# power.net
KiCad netlist of a schematic drawn in Altium Designer
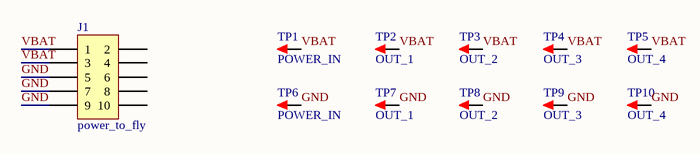
[diagram p0: power.SchDoc]

(export (version "E")
  (design (tool "Eeschema 10.0.6"))
  (components
    (comp (ref "J1")
      (value "power_to_fly")
      (footprint "HDR1.27 2x5-M-SMD")
      (description "2x5P-接插件")
      (fields (field (name "MANUFACTURER_PART_NUMBER") "826656-5"))
      (libsource (lib "mySchLib") (part "Header_2x5"))
    )
    (comp (ref "TP1")
      (value "POWER_IN")
      (footprint "test_2")
      (description "测试点")
      (fields (field (name "版权归属") "源创客"))
      (libsource (lib "Schlib") (part "TEST"))
    )
    (comp (ref "TP2")
      (value "OUT_1")
      (footprint "test_1")
      (description "测试点")
      (fields (field (name "版权归属") "源创客"))
      (libsource (lib "Schlib") (part "TEST"))
    )
    (comp (ref "TP3")
      (value "OUT_2")
      (footprint "test_1")
      (description "测试点")
      (fields (field (name "版权归属") "源创客"))
      (libsource (lib "Schlib") (part "TEST"))
    )
    (comp (ref "TP4")
      (value "OUT_3")
      (footprint "test_1")
      (description "测试点")
      (fields (field (name "版权归属") "源创客"))
      (libsource (lib "Schlib") (part "TEST"))
    )
    (comp (ref "TP5")
      (value "OUT_4")
      (footprint "test_1")
      (description "测试点")
      (fields (field (name "版权归属") "源创客"))
      (libsource (lib "Schlib") (part "TEST"))
    )
    (comp (ref "TP6")
      (value "POWER_IN")
      (footprint "test_2")
      (description "测试点")
      (fields (field (name "版权归属") "源创客"))
      (libsource (lib "Schlib") (part "TEST"))
    )
    (comp (ref "TP7")
      (value "OUT_1")
      (footprint "test_1")
      (description "测试点")
      (fields (field (name "版权归属") "源创客"))
      (libsource (lib "Schlib") (part "TEST"))
    )
    (comp (ref "TP8")
      (value "OUT_2")
      (footprint "test_1")
      (description "测试点")
      (fields (field (name "版权归属") "源创客"))
      (libsource (lib "Schlib") (part "TEST"))
    )
    (comp (ref "TP9")
      (value "OUT_3")
      (footprint "test_1")
      (description "测试点")
      (fields (field (name "版权归属") "源创客"))
      (libsource (lib "Schlib") (part "TEST"))
    )
    (comp (ref "TP10")
      (value "OUT_4")
      (footprint "test_1")
      (description "测试点")
      (fields (field (name "版权归属") "源创客"))
      (libsource (lib "Schlib") (part "TEST"))
    )
  )
  (nets
    (net (code "1") (name "/GND") (class "Default")
      (node (ref "J1") (pin "5") (pinfunction "5_5") (pintype "passive"))
      (node (ref "J1") (pin "7") (pinfunction "7_7") (pintype "passive"))
      (node (ref "J1") (pin "9") (pinfunction "9_9") (pintype "passive"))
      (node (ref "TP10") (pin "1") (pinfunction "1_1") (pintype "passive"))
      (node (ref "TP6") (pin "1") (pinfunction "1_1") (pintype "passive"))
      (node (ref "TP7") (pin "1") (pinfunction "1_1") (pintype "passive"))
      (node (ref "TP8") (pin "1") (pinfunction "1_1") (pintype "passive"))
      (node (ref "TP9") (pin "1") (pinfunction "1_1") (pintype "passive"))
    )
    (net (code "2") (name "/VBAT") (class "Default")
      (node (ref "J1") (pin "1") (pinfunction "1_1") (pintype "passive"))
      (node (ref "J1") (pin "3") (pinfunction "3_3") (pintype "passive"))
      (node (ref "TP1") (pin "1") (pinfunction "1_1") (pintype "passive"))
      (node (ref "TP2") (pin "1") (pinfunction "1_1") (pintype "passive"))
      (node (ref "TP3") (pin "1") (pinfunction "1_1") (pintype "passive"))
      (node (ref "TP4") (pin "1") (pinfunction "1_1") (pintype "passive"))
      (node (ref "TP5") (pin "1") (pinfunction "1_1") (pintype "passive"))
    )
    (net (code "3") (name "unconnected-(J1-Pad2)") (class "Default")
      (node (ref "J1") (pin "2") (pinfunction "2_2") (pintype "passive"))
    )
    (net (code "4") (name "unconnected-(J1-Pad4)") (class "Default")
      (node (ref "J1") (pin "4") (pinfunction "4_4") (pintype "passive"))
    )
    (net (code "5") (name "unconnected-(J1-Pad6)") (class "Default")
      (node (ref "J1") (pin "6") (pinfunction "6_6") (pintype "passive"))
    )
    (net (code "6") (name "unconnected-(J1-Pad8)") (class "Default")
      (node (ref "J1") (pin "8") (pinfunction "8_8") (pintype "passive"))
    )
    (net (code "7") (name "unconnected-(J1-Pad10)") (class "Default")
      (node (ref "J1") (pin "10") (pinfunction "10_10") (pintype "passive"))
    )
  )
)
